# SSB_Transceiver_IF_Amplifier.net
KiCad netlist of a schematic drawn in EAGLE
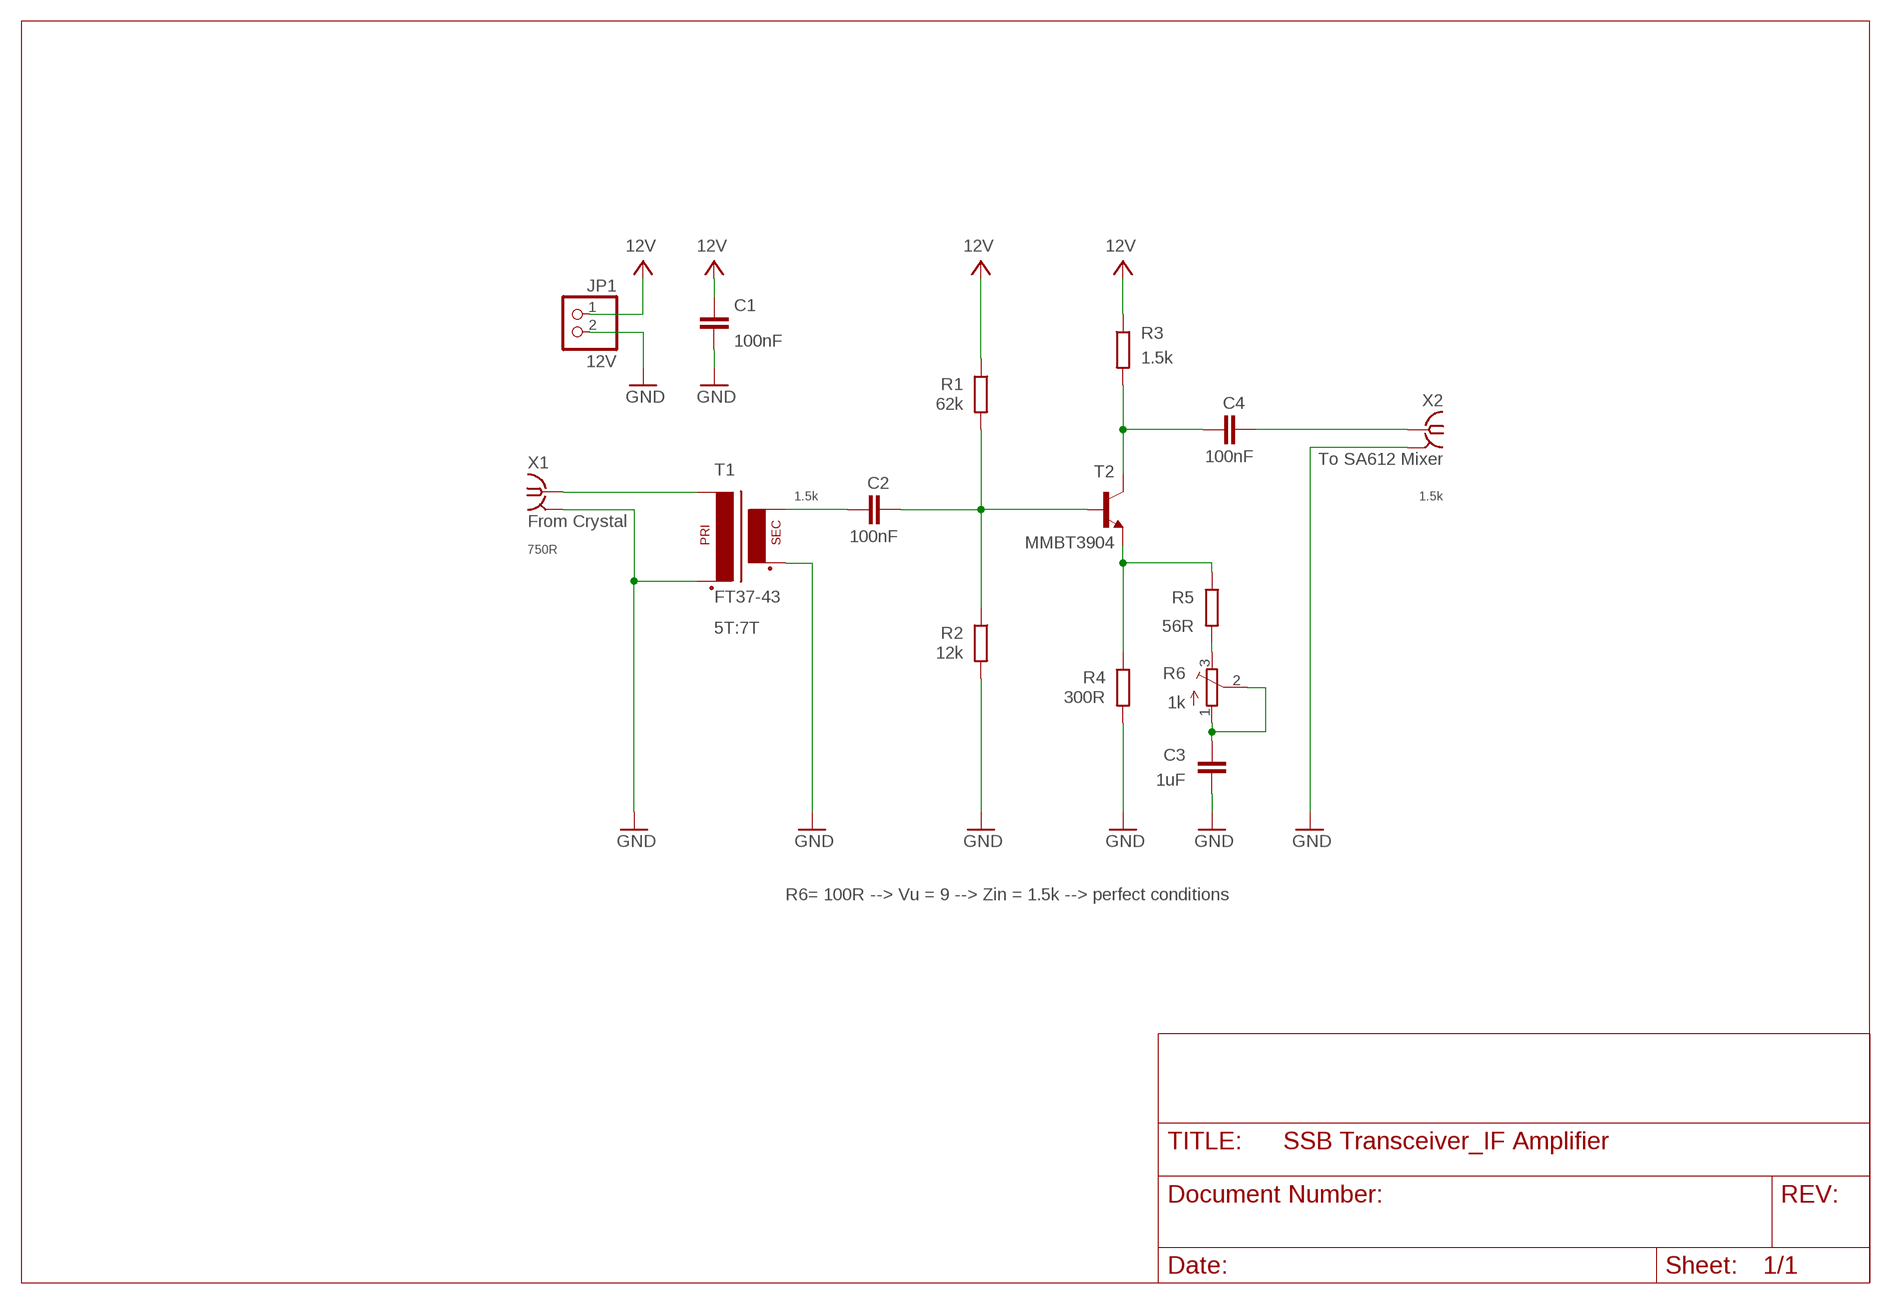
[diagram p0: schematic, sheet 1]

(export (version "E")
  (design (tool "Eeschema 10.0.6"))
  (components
    (comp (ref "C1")
      (value "100nF")
      (footprint "eagle-import:C0805")
      (libsource (lib "eagle-import") (part "C-EUC0805"))
    )
    (comp (ref "C2")
      (value "100nF")
      (footprint "eagle-import:C0805")
      (libsource (lib "eagle-import") (part "C-EUC0805"))
    )
    (comp (ref "C3")
      (value "1uF")
      (footprint "eagle-import:C0805")
      (libsource (lib "eagle-import") (part "C-EUC0805"))
    )
    (comp (ref "C4")
      (value "100nF")
      (footprint "eagle-import:C0805")
      (libsource (lib "eagle-import") (part "C-EUC0805"))
    )
    (comp (ref "JP1")
      (value "12V")
      (footprint "eagle-import:1X02")
      (libsource (lib "eagle-import") (part "PINHD-1X2"))
    )
    (comp (ref "R1")
      (value "62k")
      (footprint "eagle-import:R0805")
      (libsource (lib "eagle-import") (part "R-EU_R0805"))
    )
    (comp (ref "R2")
      (value "12k")
      (footprint "eagle-import:R0805")
      (libsource (lib "eagle-import") (part "R-EU_R0805"))
    )
    (comp (ref "R3")
      (value "1.5k")
      (footprint "eagle-import:R0805")
      (libsource (lib "eagle-import") (part "R-EU_R0805"))
    )
    (comp (ref "R4")
      (value "300R")
      (footprint "eagle-import:R0805")
      (libsource (lib "eagle-import") (part "R-EU_R0805"))
    )
    (comp (ref "R5")
      (value "56R")
      (footprint "eagle-import:R0805")
      (libsource (lib "eagle-import") (part "R-EU_R0805"))
    )
    (comp (ref "R6")
      (value "1k")
      (footprint "eagle-import:3223G")
      (libsource (lib "eagle-import") (part "TRIM_EU-3223G"))
    )
    (comp (ref "T1")
      (value "FT37-43")
      (footprint "eagle-import:FT37-43SMD")
      (libsource (lib "eagle-import") (part "FT37-43"))
    )
    (comp (ref "T2")
      (value "MMBT3904")
      (footprint "eagle-import:SOT23-BEC")
      (libsource (lib "eagle-import") (part "-NPN-SOT23-BECMMBT3904LT1"))
    )
    (comp (ref "X1")
      (value "From Crystal")
      (footprint "eagle-import:J502-ND-142-0711-821_826")
      (fields (field (name "MF") "JOHNSON COMPONENTS") (field (name "MPN") "142-0711-821"))
      (libsource (lib "eagle-import") (part "SMA-PCB-CON142-0711-821/826"))
    )
    (comp (ref "X2")
      (value "To SA612 Mixer")
      (footprint "eagle-import:J502-ND-142-0711-821_826")
      (fields (field (name "MF") "JOHNSON COMPONENTS") (field (name "MPN") "142-0711-821"))
      (libsource (lib "eagle-import") (part "SMA-PCB-CON142-0711-821/826"))
    )
  )
  (nets
    (net (code "1") (name "12V") (class "Default")
      (node (ref "C1") (pin "2") (pinfunction "2_2") (pintype "passive"))
      (node (ref "JP1") (pin "1") (pinfunction "1_1") (pintype "passive"))
      (node (ref "R1") (pin "1") (pinfunction "1_1") (pintype "passive"))
      (node (ref "R3") (pin "1") (pinfunction "1_1") (pintype "passive"))
    )
    (net (code "2") (name "GND") (class "Default")
      (node (ref "C1") (pin "1") (pinfunction "1_1") (pintype "passive"))
      (node (ref "C3") (pin "1") (pinfunction "1_1") (pintype "passive"))
      (node (ref "JP1") (pin "2") (pinfunction "2_2") (pintype "passive"))
      (node (ref "R2") (pin "2") (pinfunction "2_2") (pintype "passive"))
      (node (ref "R4") (pin "2") (pinfunction "2_2") (pintype "passive"))
      (node (ref "T1") (pin "P$2") (pinfunction "P2_P$2") (pintype "passive"))
      (node (ref "T1") (pin "S$2") (pinfunction "S2_S$2") (pintype "passive"))
      (node (ref "X1") (pin "G@1") (pinfunction "2_G@1") (pintype "passive"))
      (node (ref "X1") (pin "G@2") (pinfunction "2_G@2") (pintype "passive"))
      (node (ref "X1") (pin "G@3") (pinfunction "2_G@3") (pintype "passive"))
      (node (ref "X1") (pin "G@4") (pinfunction "2_G@4") (pintype "passive"))
      (node (ref "X2") (pin "G@1") (pinfunction "2_G@1") (pintype "passive"))
      (node (ref "X2") (pin "G@2") (pinfunction "2_G@2") (pintype "passive"))
      (node (ref "X2") (pin "G@3") (pinfunction "2_G@3") (pintype "passive"))
      (node (ref "X2") (pin "G@4") (pinfunction "2_G@4") (pintype "passive"))
    )
    (net (code "3") (name "Net-(C2-Pad2)") (class "Default")
      (node (ref "C2") (pin "2") (pinfunction "2_2") (pintype "passive"))
      (node (ref "R1") (pin "2") (pinfunction "2_2") (pintype "passive"))
      (node (ref "R2") (pin "1") (pinfunction "1_1") (pintype "passive"))
      (node (ref "T2") (pin "B") (pinfunction "B_B") (pintype "passive"))
    )
    (net (code "4") (name "Net-(C4-Pad1)") (class "Default")
      (node (ref "C4") (pin "1") (pinfunction "1_1") (pintype "passive"))
      (node (ref "R3") (pin "2") (pinfunction "2_2") (pintype "passive"))
      (node (ref "T2") (pin "C") (pinfunction "C_C") (pintype "passive"))
    )
    (net (code "5") (name "Net-(C4-Pad2)") (class "Default")
      (node (ref "C4") (pin "2") (pinfunction "2_2") (pintype "passive"))
      (node (ref "X2") (pin "1") (pinfunction "1_1") (pintype "passive"))
    )
    (net (code "6") (name "Net-(R4-Pad1)") (class "Default")
      (node (ref "R4") (pin "1") (pinfunction "1_1") (pintype "passive"))
      (node (ref "R5") (pin "1") (pinfunction "1_1") (pintype "passive"))
      (node (ref "T2") (pin "E") (pinfunction "E_E") (pintype "passive"))
    )
    (net (code "7") (name "Net-(R6-A)") (class "Default")
      (node (ref "C3") (pin "2") (pinfunction "2_2") (pintype "passive"))
      (node (ref "R6") (pin "1") (pinfunction "A_1") (pintype "passive"))
      (node (ref "R6") (pin "2") (pinfunction "S_2") (pintype "passive"))
    )
    (net (code "8") (name "Net-(R6-E)") (class "Default")
      (node (ref "R5") (pin "2") (pinfunction "2_2") (pintype "passive"))
      (node (ref "R6") (pin "3") (pinfunction "E_3") (pintype "passive"))
    )
    (net (code "9") (name "Net-(T1-P1)") (class "Default")
      (node (ref "T1") (pin "P$1") (pinfunction "P1_P$1") (pintype "passive"))
      (node (ref "X1") (pin "1") (pinfunction "1_1") (pintype "passive"))
    )
    (net (code "10") (name "Net-(T1-S1)") (class "Default")
      (node (ref "C2") (pin "1") (pinfunction "1_1") (pintype "passive"))
      (node (ref "T1") (pin "S$1") (pinfunction "S1_S$1") (pintype "passive"))
    )
  )
)
